# dmx-relay-puck.net
KiCad netlist of a schematic drawn in EAGLE
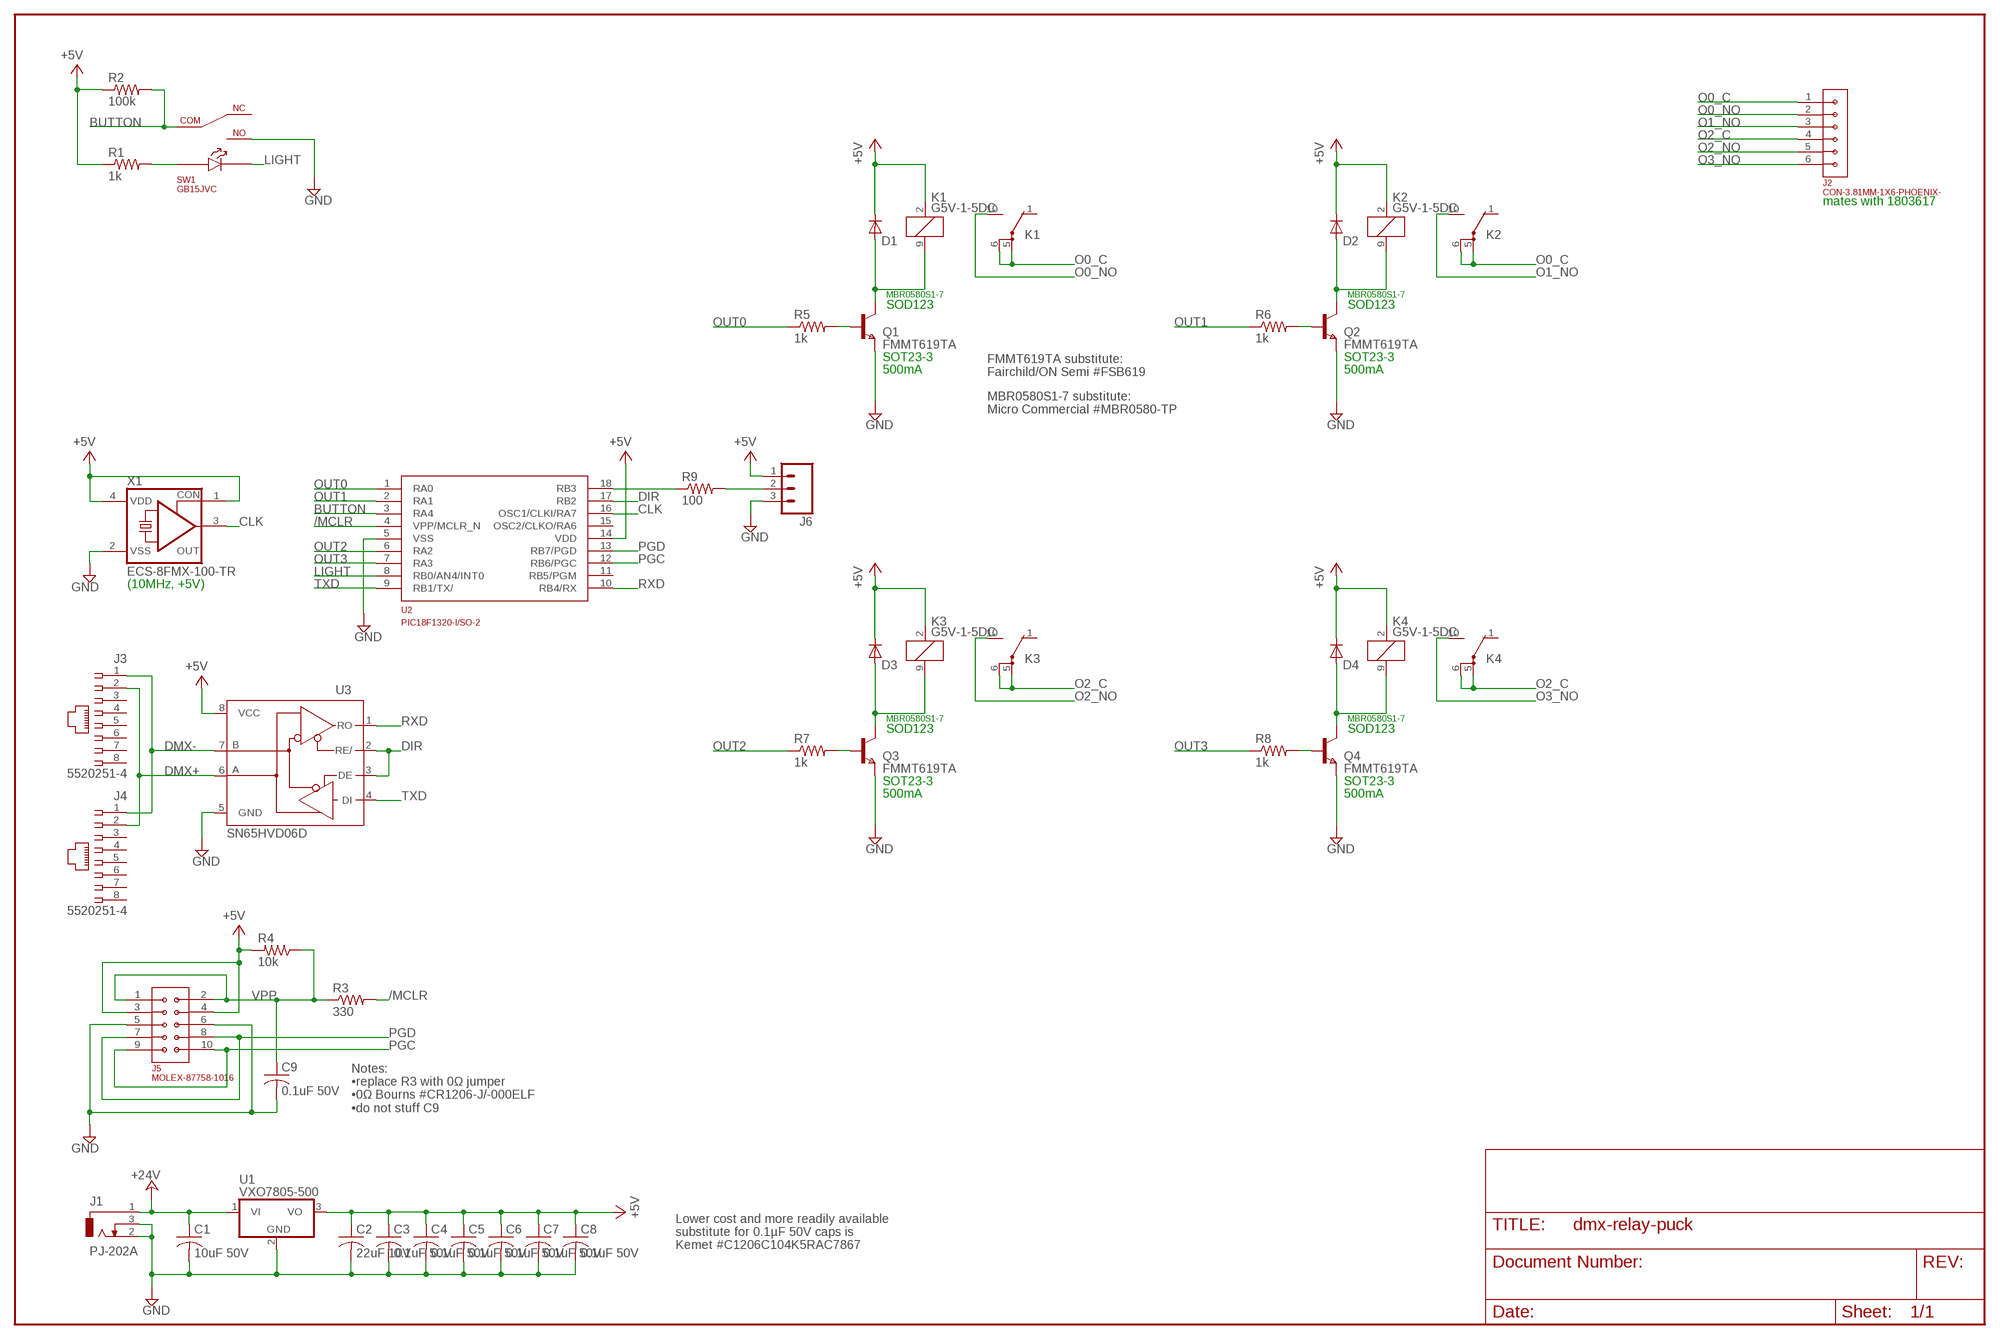
[diagram p0: schematic, sheet 1]

(export (version "E")
  (design (tool "Eeschema 10.0.6"))
  (components
    (comp (ref "C1")
      (value "10uF 50V")
      (footprint "eagle-import:C1210K")
      (fields (field (name "MFR") "KEMET") (field (name "MFR_PART_NO") "C1210C106K5RACTU"))
      (libsource (lib "eagle-import") (part "C-USC1210K"))
    )
    (comp (ref "C2")
      (value "22uF 10V")
      (footprint "eagle-import:C1206K")
      (fields (field (name "MFR") "KEMET") (field (name "MFR_PART_NO") "C1206C226K8RAC7800"))
      (libsource (lib "eagle-import") (part "C-USC1206K"))
    )
    (comp (ref "C3")
      (value "0.1uF 50V")
      (footprint "eagle-import:C1206K")
      (fields (field (name "MFR") "KEMET") (field (name "MFR_PART_NO") "C1206S104M5RACTU"))
      (libsource (lib "eagle-import") (part "C-USC1206K"))
    )
    (comp (ref "C4")
      (value "0.1uF 50V")
      (footprint "eagle-import:C1206K")
      (fields (field (name "MFR") "KEMET") (field (name "MFR_PART_NO") "C1206S104M5RACTU"))
      (libsource (lib "eagle-import") (part "C-USC1206K"))
    )
    (comp (ref "C5")
      (value "0.1uF 50V")
      (footprint "eagle-import:C1206K")
      (fields (field (name "MFR") "KEMET") (field (name "MFR_PART_NO") "C1206S104M5RACTU"))
      (libsource (lib "eagle-import") (part "C-USC1206K"))
    )
    (comp (ref "C6")
      (value "0.1uF 50V")
      (footprint "eagle-import:C1206K")
      (fields (field (name "MFR") "KEMET") (field (name "MFR_PART_NO") "C1206S104M5RACTU"))
      (libsource (lib "eagle-import") (part "C-USC1206K"))
    )
    (comp (ref "C7")
      (value "0.1uF 50V")
      (footprint "eagle-import:C1206K")
      (fields (field (name "MFR") "KEMET") (field (name "MFR_PART_NO") "C1206S104M5RACTU"))
      (libsource (lib "eagle-import") (part "C-USC1206K"))
    )
    (comp (ref "C8")
      (value "0.1uF 50V")
      (footprint "eagle-import:C1206K")
      (fields (field (name "MFR") "KEMET") (field (name "MFR_PART_NO") "C1206S104M5RACTU"))
      (libsource (lib "eagle-import") (part "C-USC1206K"))
    )
    (comp (ref "C9")
      (value "0.1uF 50V")
      (footprint "eagle-import:C1206K")
      (fields (field (name "MFR") "KEMET") (field (name "MFR_PART_NO") "C1206S104M5RACTU"))
      (libsource (lib "eagle-import") (part "C-USC1206K"))
    )
    (comp (ref "D1")
      (value "1N4148W-TP")
      (footprint "eagle-import:SOD123")
      (fields (field (name "MFR") "DIODES INC") (field (name "MFR_PART_NO") "MBR0580S1-7"))
      (libsource (lib "eagle-import") (part "DIODE-SOD123"))
    )
    (comp (ref "D2")
      (value "1N4148W-TP")
      (footprint "eagle-import:SOD123")
      (fields (field (name "MFR") "DIODES INC") (field (name "MFR_PART_NO") "MBR0580S1-7"))
      (libsource (lib "eagle-import") (part "DIODE-SOD123"))
    )
    (comp (ref "D3")
      (value "1N4148W-TP")
      (footprint "eagle-import:SOD123")
      (fields (field (name "MFR") "DIODES INC") (field (name "MFR_PART_NO") "MBR0580S1-7"))
      (libsource (lib "eagle-import") (part "DIODE-SOD123"))
    )
    (comp (ref "D4")
      (value "1N4148W-TP")
      (footprint "eagle-import:SOD123")
      (fields (field (name "MFR") "DIODES INC") (field (name "MFR_PART_NO") "MBR0580S1-7"))
      (libsource (lib "eagle-import") (part "DIODE-SOD123"))
    )
    (comp (ref "J1")
      (value "PJ-202A")
      (footprint "eagle-import:DCJ0202")
      (fields (field (name "MFR") "CUI"))
      (libsource (lib "eagle-import") (part "DCJ0202"))
    )
    (comp (ref "J2")
      (value "CON-3.81MM-1X6-PHOENIX-")
      (footprint "eagle-import:CON-PHOENIX-3.81-1X6")
      (fields (field (name "MFR") "PHOENIX") (field (name "MFR_PART_NO") "1803316"))
      (libsource (lib "eagle-import") (part "CON-3.81MM-1X6-PHOENIX-"))
    )
    (comp (ref "J3")
      (value "5520251-4")
      (footprint "eagle-import:520251-4")
      (fields (field (name "MFR") "TE"))
      (libsource (lib "eagle-import") (part "520251-4"))
    )
    (comp (ref "J4")
      (value "5520251-4")
      (footprint "eagle-import:520251-4")
      (fields (field (name "MFR") "TE"))
      (libsource (lib "eagle-import") (part "520251-4"))
    )
    (comp (ref "J5")
      (value "MOLEX-87758-1016")
      (footprint "eagle-import:CON-2MM-2X5")
      (fields (field (name "MFR") "MOLEX") (field (name "MFR_PART_NO") "87758-1016"))
      (libsource (lib "eagle-import") (part "CON-2MM-2X5-MOLEX-87758-1016"))
    )
    (comp (ref "J6")
      (value "M03PTH")
      (footprint "eagle-import:1X03")
      (fields (field (name "MFR") "WURTH") (field (name "MFR_PART_NO") "61300311121"))
      (libsource (lib "eagle-import") (part "M03PTH"))
    )
    (comp (ref "K1")
      (value "G5V-1-5DC")
      (footprint "eagle-import:G5V1")
      (fields
        (field (name "MPN") "G5V-1-DC24")
        (field (name "MFR") "OMRON")
        (field (name "MFR_PART_NO") "G5V-1-DC5")
      )
      (libsource (lib "eagle-import") (part "G5V1"))
    )
    (comp (ref "K2")
      (value "G5V-1-5DC")
      (footprint "eagle-import:G5V1")
      (fields
        (field (name "MPN") "G5V-1-DC24")
        (field (name "MFR") "OMRON")
        (field (name "MFR_PART_NO") "G5V-1-DC5")
      )
      (libsource (lib "eagle-import") (part "G5V1"))
    )
    (comp (ref "K3")
      (value "G5V-1-5DC")
      (footprint "eagle-import:G5V1")
      (fields
        (field (name "MPN") "G5V-1-DC24")
        (field (name "MFR") "OMRON")
        (field (name "MFR_PART_NO") "G5V-1-DC5")
      )
      (libsource (lib "eagle-import") (part "G5V1"))
    )
    (comp (ref "K4")
      (value "G5V-1-5DC")
      (footprint "eagle-import:G5V1")
      (fields
        (field (name "MPN") "G5V-1-DC24")
        (field (name "MFR") "OMRON")
        (field (name "MFR_PART_NO") "G5V-1-DC5")
      )
      (libsource (lib "eagle-import") (part "G5V1"))
    )
    (comp (ref "Q1")
      (value "FMMT619TA")
      (footprint "eagle-import:SOT-23")
      (fields (field (name "MPN") "DSS20201L-7") (field (name "MFR") "DIODES INC"))
      (libsource (lib "eagle-import") (part "NPNSOT23"))
    )
    (comp (ref "Q2")
      (value "FMMT619TA")
      (footprint "eagle-import:SOT-23")
      (fields (field (name "MPN") "DSS20201L-7") (field (name "MFR") "DIODES INC"))
      (libsource (lib "eagle-import") (part "NPNSOT23"))
    )
    (comp (ref "Q3")
      (value "FMMT619TA")
      (footprint "eagle-import:SOT-23")
      (fields (field (name "MPN") "DSS20201L-7") (field (name "MFR") "DIODES INC"))
      (libsource (lib "eagle-import") (part "NPNSOT23"))
    )
    (comp (ref "Q4")
      (value "FMMT619TA")
      (footprint "eagle-import:SOT-23")
      (fields (field (name "MPN") "DSS20201L-7") (field (name "MFR") "DIODES INC"))
      (libsource (lib "eagle-import") (part "NPNSOT23"))
    )
    (comp (ref "R1")
      (value "1k")
      (footprint "eagle-import:R1206")
      (fields (field (name "MFR") "BOURNS") (field (name "MFR_PART_NO") "CR1206-JW-102GLF"))
      (libsource (lib "eagle-import") (part "R-US_R1206"))
    )
    (comp (ref "R2")
      (value "100k")
      (footprint "eagle-import:R1206")
      (fields (field (name "MFR") "BOURNS") (field (name "MFR_PART_NO") "CR1206-JW-104GLF"))
      (libsource (lib "eagle-import") (part "R-US_R1206"))
    )
    (comp (ref "R3")
      (value "330")
      (footprint "eagle-import:R1206")
      (fields (field (name "MFR") "BOURNS") (field (name "MFR_PART_NO") "CR1206-JW-331ELF"))
      (libsource (lib "eagle-import") (part "R-US_R1206"))
    )
    (comp (ref "R4")
      (value "10k")
      (footprint "eagle-import:R1206")
      (fields (field (name "MFR") "BOURNS") (field (name "MFR_PART_NO") "CR1206-JW-103GLF"))
      (libsource (lib "eagle-import") (part "R-US_R1206"))
    )
    (comp (ref "R5")
      (value "1k")
      (footprint "eagle-import:R1206")
      (fields (field (name "MFR") "BOURNS") (field (name "MFR_PART_NO") "CR1206-JW-102ELF"))
      (libsource (lib "eagle-import") (part "R-US_R1206"))
    )
    (comp (ref "R6")
      (value "1k")
      (footprint "eagle-import:R1206")
      (fields (field (name "MFR") "BOURNS") (field (name "MFR_PART_NO") "CR1206-JW-102ELF"))
      (libsource (lib "eagle-import") (part "R-US_R1206"))
    )
    (comp (ref "R7")
      (value "1k")
      (footprint "eagle-import:R1206")
      (fields (field (name "MFR") "BOURNS") (field (name "MFR_PART_NO") "CR1206-JW-102ELF"))
      (libsource (lib "eagle-import") (part "R-US_R1206"))
    )
    (comp (ref "R8")
      (value "1k")
      (footprint "eagle-import:R1206")
      (fields (field (name "MFR") "BOURNS") (field (name "MFR_PART_NO") "CR1206-JW-102ELF"))
      (libsource (lib "eagle-import") (part "R-US_R1206"))
    )
    (comp (ref "R9")
      (value "100")
      (footprint "eagle-import:R1206")
      (fields (field (name "MFR") "BOURNS") (field (name "MFR_PART_NO") "CR1206-JW-101ELF"))
      (libsource (lib "eagle-import") (part "R-US_R1206"))
    )
    (comp (ref "SW1")
      (value "GB15JVC")
      (footprint "eagle-import:GB15JHC")
      (fields (field (name "MFR") "NKK"))
      (libsource (lib "eagle-import") (part "GB15JHC"))
    )
    (comp (ref "U1")
      (value "VXO7805-500")
      (footprint "eagle-import:CUI-78XX-500")
      (fields (field (name "MFR") "CUI"))
      (libsource (lib "eagle-import") (part "CUI-V7803-500"))
    )
    (comp (ref "U2")
      (value "PIC18F1320-I/SO-2")
      (footprint "eagle-import:SO18W")
      (fields (field (name "MFR") "MICROCHIP") (field (name "MFR_PART_NO") "PIC18F1320-I/SO"))
      (libsource (lib "eagle-import") (part "PIC18F1320-I/SO-2"))
    )
    (comp (ref "U3")
      (value "SN65HVD06D")
      (footprint "eagle-import:SO08")
      (fields (field (name "MPN") "MAX3468CSA+") (field (name "MFR") "TI"))
      (libsource (lib "eagle-import") (part "MAX34SA68C"))
    )
    (comp (ref "X1")
      (value "ECS-8FMX-100-TR")
      (footprint "eagle-import:1100S")
      (fields (field (name "MFR") "ECS"))
      (libsource (lib "eagle-import") (part "CRYSTAL_RES-1100S"))
    )
  )
  (nets
    (net (code "1") (name "+5V") (class "Default")
      (node (ref "C2") (pin "1") (pinfunction "1_1") (pintype "passive"))
      (node (ref "C3") (pin "1") (pinfunction "1_1") (pintype "passive"))
      (node (ref "C4") (pin "1") (pinfunction "1_1") (pintype "passive"))
      (node (ref "C5") (pin "1") (pinfunction "1_1") (pintype "passive"))
      (node (ref "C6") (pin "1") (pinfunction "1_1") (pintype "passive"))
      (node (ref "C7") (pin "1") (pinfunction "1_1") (pintype "passive"))
      (node (ref "C8") (pin "1") (pinfunction "1_1") (pintype "passive"))
      (node (ref "D1") (pin "C") (pinfunction "C_C") (pintype "passive"))
      (node (ref "D2") (pin "C") (pinfunction "C_C") (pintype "passive"))
      (node (ref "D3") (pin "C") (pinfunction "C_C") (pintype "passive"))
      (node (ref "D4") (pin "C") (pinfunction "C_C") (pintype "passive"))
      (node (ref "J5") (pin "3") (pinfunction "3_3") (pintype "bidirectional"))
      (node (ref "J5") (pin "4") (pinfunction "4_4") (pintype "bidirectional"))
      (node (ref "J6") (pin "1") (pinfunction "1_1") (pintype "passive"))
      (node (ref "K1") (pin "2") (pinfunction "1_2") (pintype "passive"))
      (node (ref "K2") (pin "2") (pinfunction "1_2") (pintype "passive"))
      (node (ref "K3") (pin "2") (pinfunction "1_2") (pintype "passive"))
      (node (ref "K4") (pin "2") (pinfunction "1_2") (pintype "passive"))
      (node (ref "R1") (pin "1") (pinfunction "1_1") (pintype "passive"))
      (node (ref "R2") (pin "1") (pinfunction "1_1") (pintype "passive"))
      (node (ref "R4") (pin "2") (pinfunction "2_2") (pintype "passive"))
      (node (ref "U1") (pin "3") (pinfunction "VO_3") (pintype "passive"))
      (node (ref "U2") (pin "14") (pinfunction "VDD_14") (pintype "bidirectional"))
      (node (ref "U3") (pin "8") (pinfunction "VCC_8") (pintype "power_in"))
      (node (ref "X1") (pin "1") (pinfunction "CON_1") (pintype "input"))
      (node (ref "X1") (pin "4") (pinfunction "VDD_4") (pintype "power_in"))
    )
    (net (code "2") (name "+24V") (class "Default")
      (node (ref "C1") (pin "1") (pinfunction "1_1") (pintype "passive"))
      (node (ref "J1") (pin "1") (pinfunction "1_1") (pintype "passive"))
      (node (ref "U1") (pin "1") (pinfunction "VI_1") (pintype "input"))
    )
    (net (code "3") (name "/BUTTON") (class "Default")
      (node (ref "R2") (pin "2") (pinfunction "2_2") (pintype "passive"))
      (node (ref "SW1") (pin "5") (pinfunction "5_5") (pintype "bidirectional"))
      (node (ref "U2") (pin "3") (pinfunction "RA4_3") (pintype "bidirectional"))
    )
    (net (code "4") (name "/CLK") (class "Default")
      (node (ref "U2") (pin "16") (pinfunction "OSC1/CLKI/RA7_16") (pintype "bidirectional"))
      (node (ref "X1") (pin "3") (pinfunction "OUT_3") (pintype "output"))
    )
    (net (code "5") (name "/DIR") (class "Default")
      (node (ref "U2") (pin "17") (pinfunction "RB2_17") (pintype "bidirectional"))
      (node (ref "U3") (pin "2") (pinfunction "RE/_2") (pintype "input"))
      (node (ref "U3") (pin "3") (pinfunction "DE_3") (pintype "input"))
    )
    (net (code "6") (name "/DMX+") (class "Default")
      (node (ref "J3") (pin "2") (pinfunction "2_2") (pintype "passive"))
      (node (ref "J4") (pin "2") (pinfunction "2_2") (pintype "passive"))
      (node (ref "U3") (pin "6") (pinfunction "A_6") (pintype "passive"))
    )
    (net (code "7") (name "/DMX-") (class "Default")
      (node (ref "J3") (pin "1") (pinfunction "1_1") (pintype "passive"))
      (node (ref "J4") (pin "1") (pinfunction "1_1") (pintype "passive"))
      (node (ref "U3") (pin "7") (pinfunction "B_7") (pintype "passive"))
    )
    (net (code "8") (name "/LIGHT") (class "Default")
      (node (ref "SW1") (pin "3") (pinfunction "3_3") (pintype "bidirectional"))
      (node (ref "U2") (pin "8") (pinfunction "RB0/AN4/INT0_8") (pintype "bidirectional"))
    )
    (net (code "9") (name "/O0_C") (class "Default")
      (node (ref "J2") (pin "1") (pinfunction "1_1") (pintype "bidirectional"))
      (node (ref "K1") (pin "5") (pinfunction "P_5") (pintype "passive"))
      (node (ref "K1") (pin "6") (pinfunction "P_6") (pintype "passive"))
      (node (ref "K2") (pin "5") (pinfunction "P_5") (pintype "passive"))
      (node (ref "K2") (pin "6") (pinfunction "P_6") (pintype "passive"))
    )
    (net (code "10") (name "/O0_NO") (class "Default")
      (node (ref "J2") (pin "2") (pinfunction "2_2") (pintype "bidirectional"))
      (node (ref "K1") (pin "10") (pinfunction "S_10") (pintype "passive"))
    )
    (net (code "11") (name "/O1_NO") (class "Default")
      (node (ref "J2") (pin "3") (pinfunction "3_3") (pintype "bidirectional"))
      (node (ref "K2") (pin "10") (pinfunction "S_10") (pintype "passive"))
    )
    (net (code "12") (name "/O2_C") (class "Default")
      (node (ref "J2") (pin "4") (pinfunction "4_4") (pintype "bidirectional"))
      (node (ref "K3") (pin "5") (pinfunction "P_5") (pintype "passive"))
      (node (ref "K3") (pin "6") (pinfunction "P_6") (pintype "passive"))
      (node (ref "K4") (pin "5") (pinfunction "P_5") (pintype "passive"))
      (node (ref "K4") (pin "6") (pinfunction "P_6") (pintype "passive"))
    )
    (net (code "13") (name "/O2_NO") (class "Default")
      (node (ref "J2") (pin "5") (pinfunction "5_5") (pintype "bidirectional"))
      (node (ref "K3") (pin "10") (pinfunction "S_10") (pintype "passive"))
    )
    (net (code "14") (name "/O3_NO") (class "Default")
      (node (ref "J2") (pin "6") (pinfunction "6_6") (pintype "bidirectional"))
      (node (ref "K4") (pin "10") (pinfunction "S_10") (pintype "passive"))
    )
    (net (code "15") (name "/OUT0") (class "Default")
      (node (ref "R5") (pin "1") (pinfunction "1_1") (pintype "passive"))
      (node (ref "U2") (pin "1") (pinfunction "RA0_1") (pintype "bidirectional"))
    )
    (net (code "16") (name "/OUT1") (class "Default")
      (node (ref "R6") (pin "1") (pinfunction "1_1") (pintype "passive"))
      (node (ref "U2") (pin "2") (pinfunction "RA1_2") (pintype "bidirectional"))
    )
    (net (code "17") (name "/OUT2") (class "Default")
      (node (ref "R7") (pin "1") (pinfunction "1_1") (pintype "passive"))
      (node (ref "U2") (pin "6") (pinfunction "RA2_6") (pintype "bidirectional"))
    )
    (net (code "18") (name "/OUT3") (class "Default")
      (node (ref "R8") (pin "1") (pinfunction "1_1") (pintype "passive"))
      (node (ref "U2") (pin "7") (pinfunction "RA3_7") (pintype "bidirectional"))
    )
    (net (code "19") (name "/PGC") (class "Default")
      (node (ref "J5") (pin "10") (pinfunction "10_10") (pintype "bidirectional"))
      (node (ref "J5") (pin "9") (pinfunction "9_9") (pintype "bidirectional"))
      (node (ref "U2") (pin "12") (pinfunction "RB6/PGC_12") (pintype "bidirectional"))
    )
    (net (code "20") (name "/PGD") (class "Default")
      (node (ref "J5") (pin "7") (pinfunction "7_7") (pintype "bidirectional"))
      (node (ref "J5") (pin "8") (pinfunction "8_8") (pintype "bidirectional"))
      (node (ref "U2") (pin "13") (pinfunction "RB7/PGD_13") (pintype "bidirectional"))
    )
    (net (code "21") (name "/RXD") (class "Default")
      (node (ref "U2") (pin "10") (pinfunction "RB4/RX_10") (pintype "bidirectional"))
      (node (ref "U3") (pin "1") (pinfunction "RO_1") (pintype "output"))
    )
    (net (code "22") (name "/TXD") (class "Default")
      (node (ref "U2") (pin "9") (pinfunction "RB1/TX/_9") (pintype "bidirectional"))
      (node (ref "U3") (pin "4") (pinfunction "DI_4") (pintype "input"))
    )
    (net (code "23") (name "/VPP") (class "Default")
      (node (ref "C9") (pin "1") (pinfunction "1_1") (pintype "passive"))
      (node (ref "J5") (pin "1") (pinfunction "1_1") (pintype "bidirectional"))
      (node (ref "J5") (pin "2") (pinfunction "2_2") (pintype "bidirectional"))
      (node (ref "R3") (pin "1") (pinfunction "1_1") (pintype "passive"))
      (node (ref "R4") (pin "1") (pinfunction "1_1") (pintype "passive"))
    )
    (net (code "24") (name "/{slash}MCLR") (class "Default")
      (node (ref "R3") (pin "2") (pinfunction "2_2") (pintype "passive"))
      (node (ref "U2") (pin "4") (pinfunction "VPP/MCLR_N_4") (pintype "bidirectional"))
    )
    (net (code "25") (name "GND") (class "Default")
      (node (ref "C1") (pin "2") (pinfunction "2_2") (pintype "passive"))
      (node (ref "C2") (pin "2") (pinfunction "2_2") (pintype "passive"))
      (node (ref "C3") (pin "2") (pinfunction "2_2") (pintype "passive"))
      (node (ref "C4") (pin "2") (pinfunction "2_2") (pintype "passive"))
      (node (ref "C5") (pin "2") (pinfunction "2_2") (pintype "passive"))
      (node (ref "C6") (pin "2") (pinfunction "2_2") (pintype "passive"))
      (node (ref "C7") (pin "2") (pinfunction "2_2") (pintype "passive"))
      (node (ref "C8") (pin "2") (pinfunction "2_2") (pintype "passive"))
      (node (ref "C9") (pin "2") (pinfunction "2_2") (pintype "passive"))
      (node (ref "J1") (pin "2") (pinfunction "2_2") (pintype "passive"))
      (node (ref "J1") (pin "3") (pinfunction "3_3") (pintype "passive"))
      (node (ref "J5") (pin "5") (pinfunction "5_5") (pintype "bidirectional"))
      (node (ref "J5") (pin "6") (pinfunction "6_6") (pintype "bidirectional"))
      (node (ref "J6") (pin "3") (pinfunction "3_3") (pintype "passive"))
      (node (ref "Q1") (pin "2") (pinfunction "E_2") (pintype "passive"))
      (node (ref "Q2") (pin "2") (pinfunction "E_2") (pintype "passive"))
      (node (ref "Q3") (pin "2") (pinfunction "E_2") (pintype "passive"))
      (node (ref "Q4") (pin "2") (pinfunction "E_2") (pintype "passive"))
      (node (ref "SW1") (pin "4") (pinfunction "4_4") (pintype "bidirectional"))
      (node (ref "U1") (pin "2") (pinfunction "GND_2") (pintype "passive"))
      (node (ref "U2") (pin "5") (pinfunction "VSS_5") (pintype "bidirectional"))
      (node (ref "U3") (pin "5") (pinfunction "GND_5") (pintype "power_in"))
      (node (ref "X1") (pin "2") (pinfunction "VSS_2") (pintype "power_in"))
    )
    (net (code "26") (name "Net-(J6-Pad2)") (class "Default")
      (node (ref "J6") (pin "2") (pinfunction "2_2") (pintype "passive"))
      (node (ref "R9") (pin "2") (pinfunction "2_2") (pintype "passive"))
    )
    (net (code "27") (name "Net-(K1A-2)") (class "Default")
      (node (ref "D1") (pin "A") (pinfunction "A_A") (pintype "passive"))
      (node (ref "K1") (pin "9") (pinfunction "2_9") (pintype "passive"))
      (node (ref "Q1") (pin "1") (pinfunction "C_1") (pintype "passive"))
    )
    (net (code "28") (name "Net-(K2A-2)") (class "Default")
      (node (ref "D2") (pin "A") (pinfunction "A_A") (pintype "passive"))
      (node (ref "K2") (pin "9") (pinfunction "2_9") (pintype "passive"))
      (node (ref "Q2") (pin "1") (pinfunction "C_1") (pintype "passive"))
    )
    (net (code "29") (name "Net-(K3A-2)") (class "Default")
      (node (ref "D3") (pin "A") (pinfunction "A_A") (pintype "passive"))
      (node (ref "K3") (pin "9") (pinfunction "2_9") (pintype "passive"))
      (node (ref "Q3") (pin "1") (pinfunction "C_1") (pintype "passive"))
    )
    (net (code "30") (name "Net-(K4A-2)") (class "Default")
      (node (ref "D4") (pin "A") (pinfunction "A_A") (pintype "passive"))
      (node (ref "K4") (pin "9") (pinfunction "2_9") (pintype "passive"))
      (node (ref "Q4") (pin "1") (pinfunction "C_1") (pintype "passive"))
    )
    (net (code "31") (name "Net-(Q1-B)") (class "Default")
      (node (ref "Q1") (pin "3") (pinfunction "B_3") (pintype "passive"))
      (node (ref "R5") (pin "2") (pinfunction "2_2") (pintype "passive"))
    )
    (net (code "32") (name "Net-(Q2-B)") (class "Default")
      (node (ref "Q2") (pin "3") (pinfunction "B_3") (pintype "passive"))
      (node (ref "R6") (pin "2") (pinfunction "2_2") (pintype "passive"))
    )
    (net (code "33") (name "Net-(Q3-B)") (class "Default")
      (node (ref "Q3") (pin "3") (pinfunction "B_3") (pintype "passive"))
      (node (ref "R7") (pin "2") (pinfunction "2_2") (pintype "passive"))
    )
    (net (code "34") (name "Net-(Q4-B)") (class "Default")
      (node (ref "Q4") (pin "3") (pinfunction "B_3") (pintype "passive"))
      (node (ref "R8") (pin "2") (pinfunction "2_2") (pintype "passive"))
    )
    (net (code "35") (name "Net-(R1-Pad2)") (class "Default")
      (node (ref "R1") (pin "2") (pinfunction "2_2") (pintype "passive"))
      (node (ref "SW1") (pin "1") (pinfunction "1_1") (pintype "bidirectional"))
    )
    (net (code "36") (name "Net-(U2-RB3)") (class "Default")
      (node (ref "R9") (pin "1") (pinfunction "1_1") (pintype "passive"))
      (node (ref "U2") (pin "18") (pinfunction "RB3_18") (pintype "bidirectional"))
    )
    (net (code "37") (name "unconnected-(J3-Pad3)") (class "Default")
      (node (ref "J3") (pin "3") (pinfunction "3_3") (pintype "passive"))
    )
    (net (code "38") (name "unconnected-(J3-Pad4)") (class "Default")
      (node (ref "J3") (pin "4") (pinfunction "4_4") (pintype "passive"))
    )
    (net (code "39") (name "unconnected-(J3-Pad5)") (class "Default")
      (node (ref "J3") (pin "5") (pinfunction "5_5") (pintype "passive"))
    )
    (net (code "40") (name "unconnected-(J3-Pad6)") (class "Default")
      (node (ref "J3") (pin "6") (pinfunction "6_6") (pintype "passive"))
    )
    (net (code "41") (name "unconnected-(J3-Pad7)") (class "Default")
      (node (ref "J3") (pin "7") (pinfunction "7_7") (pintype "passive"))
    )
    (net (code "42") (name "unconnected-(J3-Pad8)") (class "Default")
      (node (ref "J3") (pin "8") (pinfunction "8_8") (pintype "passive"))
    )
    (net (code "43") (name "unconnected-(J4-Pad3)") (class "Default")
      (node (ref "J4") (pin "3") (pinfunction "3_3") (pintype "passive"))
    )
    (net (code "44") (name "unconnected-(J4-Pad4)") (class "Default")
      (node (ref "J4") (pin "4") (pinfunction "4_4") (pintype "passive"))
    )
    (net (code "45") (name "unconnected-(J4-Pad5)") (class "Default")
      (node (ref "J4") (pin "5") (pinfunction "5_5") (pintype "passive"))
    )
    (net (code "46") (name "unconnected-(J4-Pad6)") (class "Default")
      (node (ref "J4") (pin "6") (pinfunction "6_6") (pintype "passive"))
    )
    (net (code "47") (name "unconnected-(J4-Pad7)") (class "Default")
      (node (ref "J4") (pin "7") (pinfunction "7_7") (pintype "passive"))
    )
    (net (code "48") (name "unconnected-(J4-Pad8)") (class "Default")
      (node (ref "J4") (pin "8") (pinfunction "8_8") (pintype "passive"))
    )
    (net (code "49") (name "unconnected-(K1B-O-Pad1)") (class "Default")
      (node (ref "K1") (pin "1") (pinfunction "O_1") (pintype "passive"))
    )
    (net (code "50") (name "unconnected-(K2B-O-Pad1)") (class "Default")
      (node (ref "K2") (pin "1") (pinfunction "O_1") (pintype "passive"))
    )
    (net (code "51") (name "unconnected-(K3B-O-Pad1)") (class "Default")
      (node (ref "K3") (pin "1") (pinfunction "O_1") (pintype "passive"))
    )
    (net (code "52") (name "unconnected-(K4B-O-Pad1)") (class "Default")
      (node (ref "K4") (pin "1") (pinfunction "O_1") (pintype "passive"))
    )
    (net (code "53") (name "unconnected-(SW1-Pad6)") (class "Default")
      (node (ref "SW1") (pin "6") (pinfunction "6_6") (pintype "bidirectional"))
    )
    (net (code "54") (name "unconnected-(U2-OSC2{slash}CLKO{slash}RA6-Pad15)") (class "Default")
      (node (ref "U2") (pin "15") (pinfunction "OSC2/CLKO/RA6_15") (pintype "bidirectional"))
    )
    (net (code "55") (name "unconnected-(U2-RB5{slash}PGM-Pad11)") (class "Default")
      (node (ref "U2") (pin "11") (pinfunction "RB5/PGM_11") (pintype "bidirectional"))
    )
  )
)
